# light_emitter.net
KiCad netlist of a schematic drawn in EAGLE
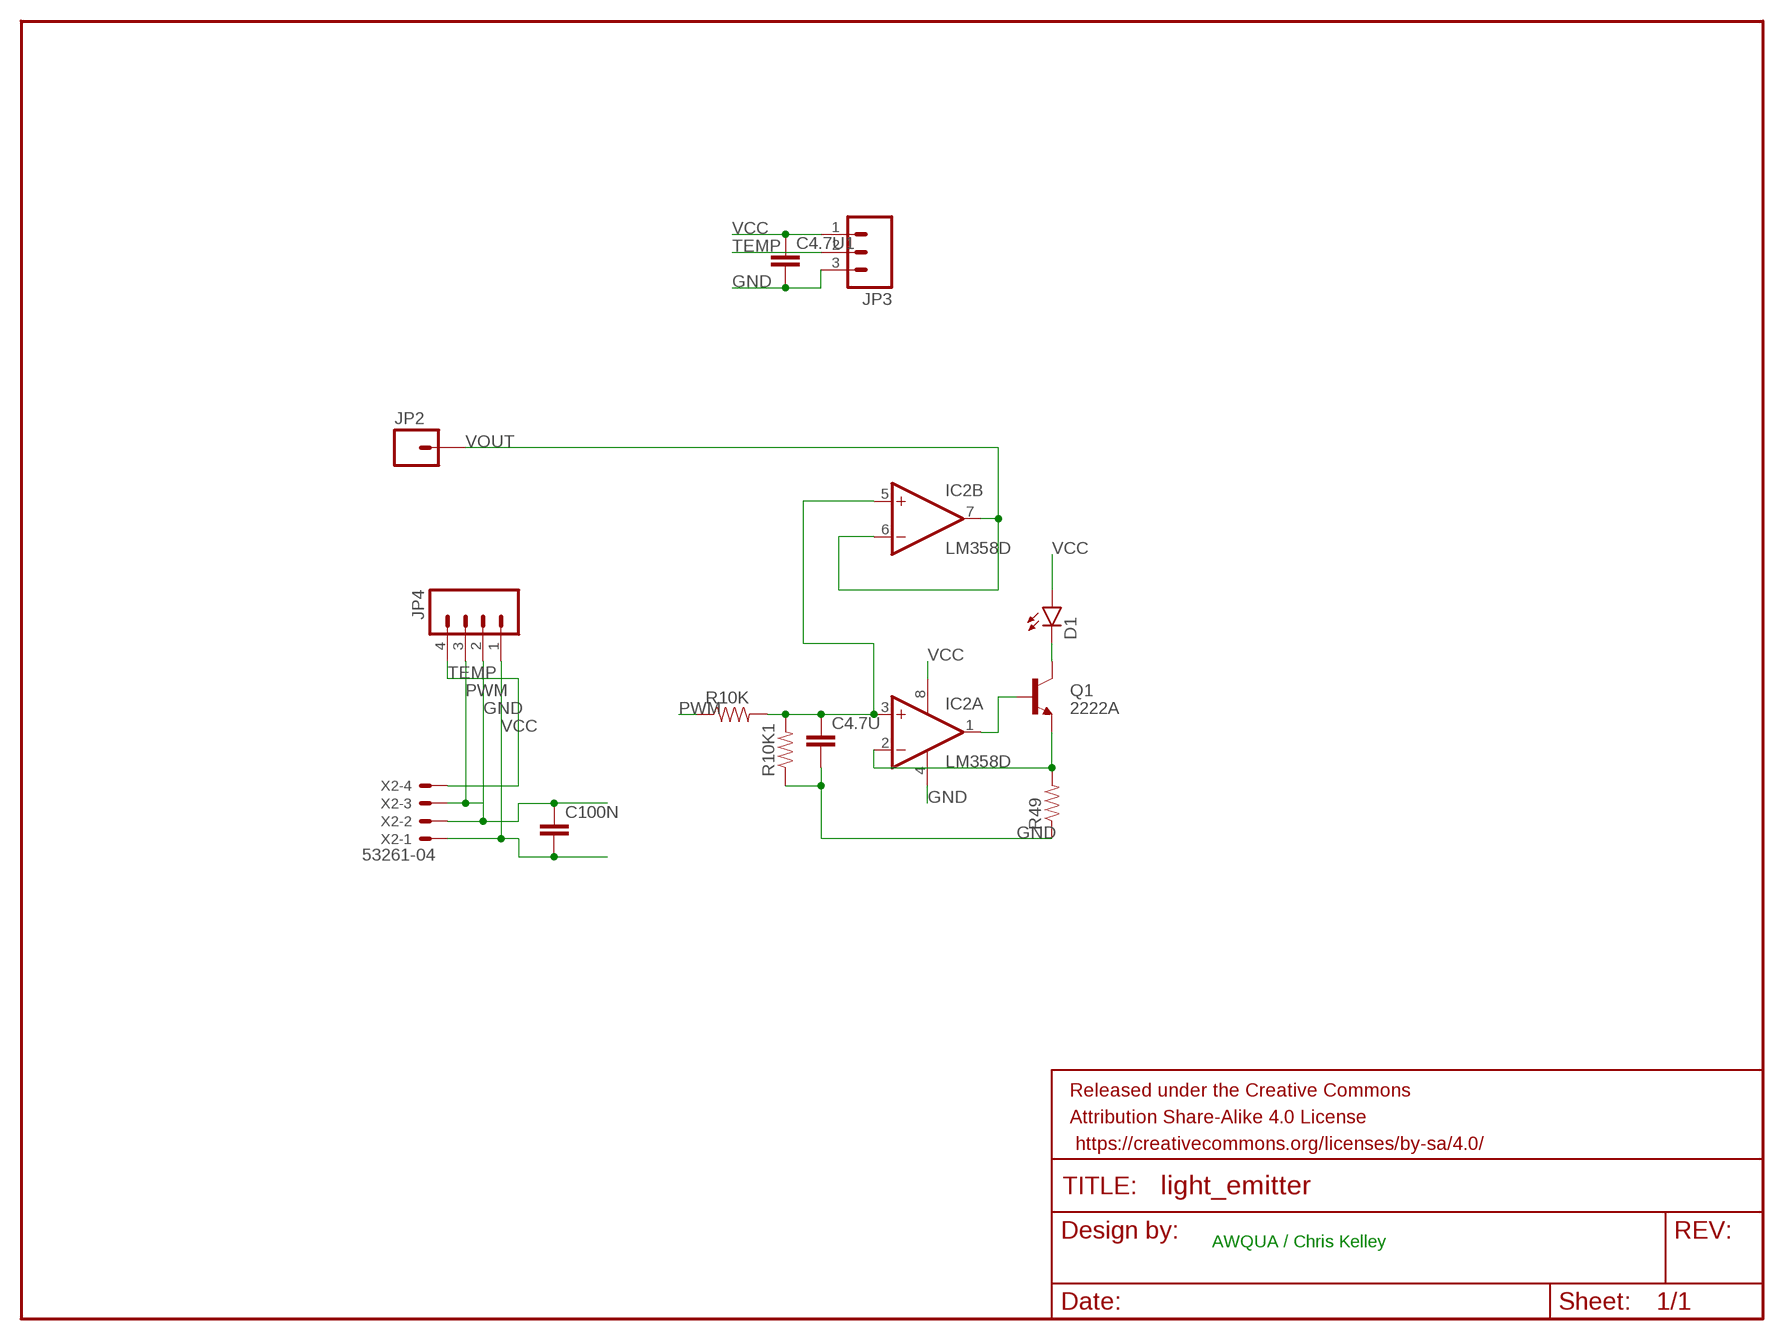
[diagram p0: schematic, sheet 1]

(export (version "E")
  (design (tool "Eeschema 10.0.6"))
  (components
    (comp (ref "C4.7U")
      (value "CAP0603-CAP")
      (footprint "eagle-import:0603-CAP")
      (libsource (lib "eagle-import") (part "CAP0603-CAP"))
    )
    (comp (ref "C4.7U1")
      (value "CAP0603-CAP")
      (footprint "eagle-import:0603-CAP")
      (libsource (lib "eagle-import") (part "CAP0603-CAP"))
    )
    (comp (ref "C100N")
      (value "CAP0603-CAP")
      (footprint "eagle-import:0603-CAP")
      (libsource (lib "eagle-import") (part "CAP0603-CAP"))
    )
    (comp (ref "D1")
      (value "LED5MM")
      (footprint "eagle-import:LED5MM")
      (libsource (lib "eagle-import") (part "LED5MM"))
    )
    (comp (ref "FRAME1")
      (value "FRAME-LETTER")
      (footprint "eagle-import:CREATIVE_COMMONS")
      (libsource (lib "eagle-import") (part "FRAME-LETTER"))
    )
    (comp (ref "IC2")
      (value "LM358D")
      (footprint "eagle-import:SO08")
      (libsource (lib "eagle-import") (part "LM358D"))
    )
    (comp (ref "JP2")
      (value "M01PTH")
      (footprint "eagle-import:1X01")
      (libsource (lib "eagle-import") (part "M01PTH"))
    )
    (comp (ref "JP3")
      (value "M03PTH")
      (footprint "eagle-import:1X03")
      (libsource (lib "eagle-import") (part "M03PTH"))
    )
    (comp (ref "JP4")
      (value "M04PTH")
      (footprint "eagle-import:1X04")
      (libsource (lib "eagle-import") (part "M04PTH"))
    )
    (comp (ref "Q1")
      (value "2222A")
      (footprint "eagle-import:SOT23-3")
      (libsource (lib "eagle-import") (part "TRANSISTOR_NPNMMBT2222A"))
    )
    (comp (ref "R10K")
      (value "RESISTOR0603-RES")
      (footprint "eagle-import:0603-RES")
      (libsource (lib "eagle-import") (part "RESISTOR0603-RES"))
    )
    (comp (ref "R10K1")
      (value "RESISTOR0603-RES")
      (footprint "eagle-import:0603-RES")
      (libsource (lib "eagle-import") (part "RESISTOR0603-RES"))
    )
    (comp (ref "R49")
      (value "RESISTOR0603-RES")
      (footprint "eagle-import:0603-RES")
      (libsource (lib "eagle-import") (part "RESISTOR0603-RES"))
    )
    (comp (ref "X2")
      (value "53261-04")
      (footprint "eagle-import:53261-04")
      (libsource (lib "eagle-import") (part "53?-04261"))
    )
  )
  (nets
    (net (code "1") (name "/GND") (class "Default")
      (node (ref "C100N") (pin "1") (pinfunction "1_1") (pintype "passive"))
      (node (ref "C4.7U") (pin "2") (pinfunction "2_2") (pintype "passive"))
      (node (ref "C4.7U1") (pin "2") (pinfunction "2_2") (pintype "passive"))
      (node (ref "IC2") (pin "4") (pinfunction "V-_4") (pintype "power_in"))
      (node (ref "JP3") (pin "3") (pinfunction "3_3") (pintype "passive"))
      (node (ref "JP4") (pin "2") (pinfunction "2_2") (pintype "passive"))
      (node (ref "R10K1") (pin "1") (pinfunction "1_1") (pintype "passive"))
      (node (ref "R49") (pin "1") (pinfunction "1_1") (pintype "passive"))
      (node (ref "X2") (pin "2") (pinfunction "S_2") (pintype "passive"))
    )
    (net (code "2") (name "/PWM") (class "Default")
      (node (ref "JP4") (pin "3") (pinfunction "3_3") (pintype "passive"))
      (node (ref "R10K") (pin "1") (pinfunction "1_1") (pintype "passive"))
      (node (ref "X2") (pin "3") (pinfunction "S_3") (pintype "passive"))
    )
    (net (code "3") (name "/TEMP") (class "Default")
      (node (ref "JP3") (pin "2") (pinfunction "2_2") (pintype "passive"))
      (node (ref "JP4") (pin "4") (pinfunction "4_4") (pintype "passive"))
      (node (ref "X2") (pin "4") (pinfunction "S_4") (pintype "passive"))
    )
    (net (code "4") (name "/VCC") (class "Default")
      (node (ref "C100N") (pin "2") (pinfunction "2_2") (pintype "passive"))
      (node (ref "C4.7U1") (pin "1") (pinfunction "1_1") (pintype "passive"))
      (node (ref "D1") (pin "A") (pinfunction "A_A") (pintype "passive"))
      (node (ref "IC2") (pin "8") (pinfunction "V+_8") (pintype "power_in"))
      (node (ref "JP3") (pin "1") (pinfunction "1_1") (pintype "passive"))
      (node (ref "JP4") (pin "1") (pinfunction "1_1") (pintype "passive"))
      (node (ref "X2") (pin "1") (pinfunction "S_1") (pintype "passive"))
    )
    (net (code "5") (name "/VOUT") (class "Default")
      (node (ref "IC2") (pin "6") (pinfunction "-IN_6") (pintype "input"))
      (node (ref "IC2") (pin "7") (pinfunction "OUT_7") (pintype "output"))
      (node (ref "JP2") (pin "1") (pinfunction "1_1") (pintype "passive"))
    )
    (net (code "6") (name "Net-(D1-C)") (class "Default")
      (node (ref "D1") (pin "K") (pinfunction "C_K") (pintype "passive"))
      (node (ref "Q1") (pin "3") (pinfunction "C_3") (pintype "passive"))
    )
    (net (code "7") (name "Net-(IC2A-+IN)") (class "Default")
      (node (ref "C4.7U") (pin "1") (pinfunction "1_1") (pintype "passive"))
      (node (ref "IC2") (pin "3") (pinfunction "+IN_3") (pintype "input"))
      (node (ref "IC2") (pin "5") (pinfunction "+IN_5") (pintype "input"))
      (node (ref "R10K") (pin "2") (pinfunction "2_2") (pintype "passive"))
      (node (ref "R10K1") (pin "2") (pinfunction "2_2") (pintype "passive"))
    )
    (net (code "8") (name "Net-(IC2A--IN)") (class "Default")
      (node (ref "IC2") (pin "2") (pinfunction "-IN_2") (pintype "input"))
      (node (ref "Q1") (pin "2") (pinfunction "E_2") (pintype "passive"))
      (node (ref "R49") (pin "2") (pinfunction "2_2") (pintype "passive"))
    )
    (net (code "9") (name "Net-(IC2A-OUT)") (class "Default")
      (node (ref "IC2") (pin "1") (pinfunction "OUT_1") (pintype "output"))
      (node (ref "Q1") (pin "1") (pinfunction "B_1") (pintype "passive"))
    )
  )
)
